# ADC_Driver.net
KiCad netlist of a schematic drawn in Altium Designer
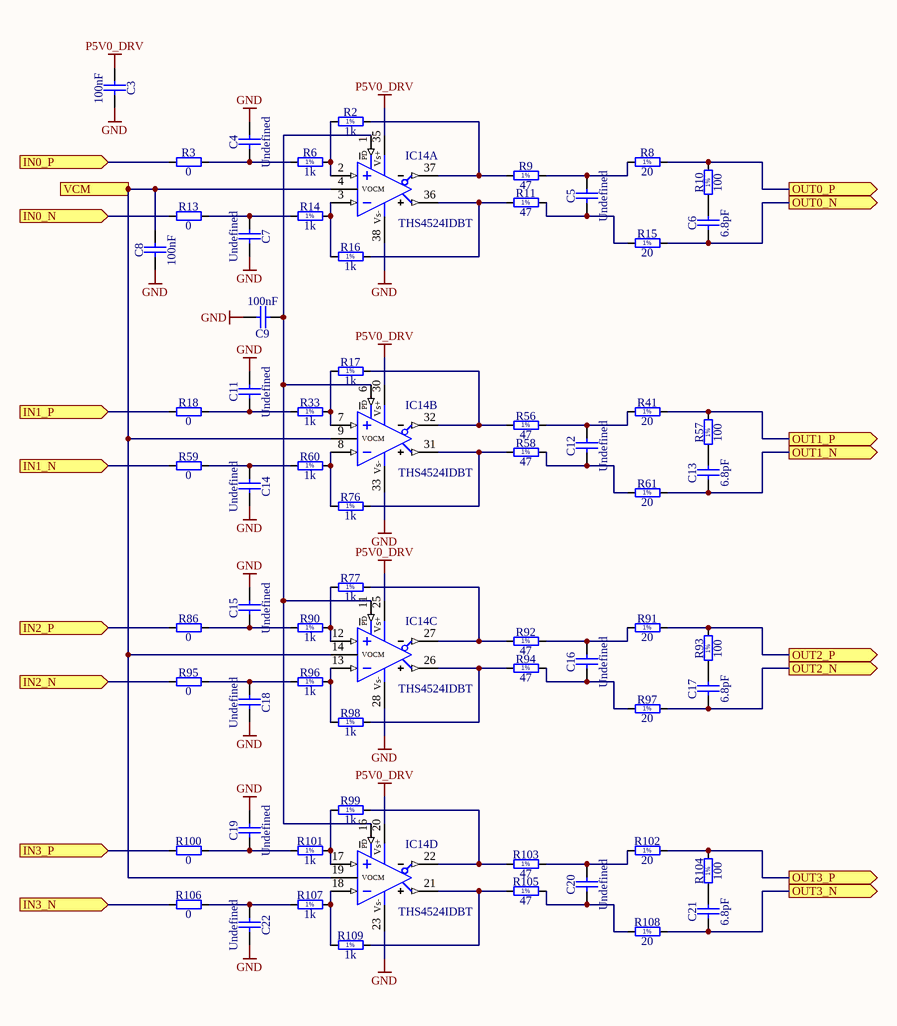
[diagram p0: ADC_Driver.SchDoc]

(export (version "E")
  (design (tool "Eeschema 10.0.6"))
  (components
    (comp (ref "C3")
      (value "100nF")
      (footprint "CAPC0603X33N")
      (description "Non-polarised capacitor")
      (fields
        (field (name "PART NUMBER") "CC0201_100NF_6.3V_10%_X5R")
        (field (name "VOLTAGE") "6.3V")
        (field (name "AUTHOR") "CERN DEM JLC")
      )
      (libsource (lib "Capacitors") (part "Capacitor - non polarized"))
    )
    (comp (ref "C4")
      (value "Undefined")
      (footprint "CAPC1005X55N")
      (description "Non-polarised capacitor")
      (fields (field (name "PART NUMBER") "CC0402_NO-VALUE") (field (name "AUTHOR") "CERN DEM JLC"))
      (libsource (lib "Capacitors") (part "Capacitor - non polarized"))
    )
    (comp (ref "C5")
      (value "Undefined")
      (footprint "CAPC1005X55N")
      (description "Non-polarised capacitor")
      (fields (field (name "PART NUMBER") "CC0402_NO-VALUE") (field (name "AUTHOR") "CERN DEM JLC"))
      (libsource (lib "Capacitors") (part "Capacitor - non polarized"))
    )
    (comp (ref "C6")
      (value "6.8pF")
      (footprint "CAPC1005X70N")
      (description "Non-polarised capacitor")
      (fields
        (field (name "PART NUMBER") "CC0402_6.8PF_50V_0.25PF_C0G_VISHAY_VJ_NON-MAGNETIC")
        (field (name "VOLTAGE") "50V")
        (field (name "AUTHOR") "CERN DEM MR")
      )
      (libsource (lib "Capacitors") (part "Capacitor - non polarized"))
    )
    (comp (ref "C7")
      (value "Undefined")
      (footprint "CAPC1005X55N")
      (description "Non-polarised capacitor")
      (fields (field (name "PART NUMBER") "CC0402_NO-VALUE") (field (name "AUTHOR") "CERN DEM JLC"))
      (libsource (lib "Capacitors") (part "Capacitor - non polarized"))
    )
    (comp (ref "C8")
      (value "100nF")
      (footprint "CAPC0603X33N")
      (description "Non-polarised capacitor")
      (fields
        (field (name "PART NUMBER") "CC0201_100NF_6.3V_10%_X5R")
        (field (name "VOLTAGE") "6.3V")
        (field (name "AUTHOR") "CERN DEM JLC")
      )
      (libsource (lib "Capacitors") (part "Capacitor - non polarized"))
    )
    (comp (ref "C9")
      (value "100nF")
      (footprint "CAPC0603X33N")
      (description "Non-polarised capacitor")
      (fields
        (field (name "PART NUMBER") "CC0201_100NF_6.3V_10%_X5R")
        (field (name "VOLTAGE") "6.3V")
        (field (name "AUTHOR") "CERN DEM JLC")
      )
      (libsource (lib "Capacitors") (part "Capacitor - non polarized"))
    )
    (comp (ref "C11")
      (value "Undefined")
      (footprint "CAPC1005X55N")
      (description "Non-polarised capacitor")
      (fields (field (name "PART NUMBER") "CC0402_NO-VALUE") (field (name "AUTHOR") "CERN DEM JLC"))
      (libsource (lib "Capacitors") (part "Capacitor - non polarized"))
    )
    (comp (ref "C12")
      (value "Undefined")
      (footprint "CAPC1005X55N")
      (description "Non-polarised capacitor")
      (fields (field (name "PART NUMBER") "CC0402_NO-VALUE") (field (name "AUTHOR") "CERN DEM JLC"))
      (libsource (lib "Capacitors") (part "Capacitor - non polarized"))
    )
    (comp (ref "C13")
      (value "6.8pF")
      (footprint "CAPC1005X70N")
      (description "Non-polarised capacitor")
      (fields
        (field (name "PART NUMBER") "CC0402_6.8PF_50V_0.25PF_C0G_VISHAY_VJ_NON-MAGNETIC")
        (field (name "VOLTAGE") "50V")
        (field (name "AUTHOR") "CERN DEM MR")
      )
      (libsource (lib "Capacitors") (part "Capacitor - non polarized"))
    )
    (comp (ref "C14")
      (value "Undefined")
      (footprint "CAPC1005X55N")
      (description "Non-polarised capacitor")
      (fields (field (name "PART NUMBER") "CC0402_NO-VALUE") (field (name "AUTHOR") "CERN DEM JLC"))
      (libsource (lib "Capacitors") (part "Capacitor - non polarized"))
    )
    (comp (ref "C15")
      (value "Undefined")
      (footprint "CAPC1005X55N")
      (description "Non-polarised capacitor")
      (fields (field (name "PART NUMBER") "CC0402_NO-VALUE") (field (name "AUTHOR") "CERN DEM JLC"))
      (libsource (lib "Capacitors") (part "Capacitor - non polarized"))
    )
    (comp (ref "C16")
      (value "Undefined")
      (footprint "CAPC1005X55N")
      (description "Non-polarised capacitor")
      (fields (field (name "PART NUMBER") "CC0402_NO-VALUE") (field (name "AUTHOR") "CERN DEM JLC"))
      (libsource (lib "Capacitors") (part "Capacitor - non polarized"))
    )
    (comp (ref "C17")
      (value "6.8pF")
      (footprint "CAPC1005X70N")
      (description "Non-polarised capacitor")
      (fields
        (field (name "PART NUMBER") "CC0402_6.8PF_50V_0.25PF_C0G_VISHAY_VJ_NON-MAGNETIC")
        (field (name "VOLTAGE") "50V")
        (field (name "AUTHOR") "CERN DEM MR")
      )
      (libsource (lib "Capacitors") (part "Capacitor - non polarized"))
    )
    (comp (ref "C18")
      (value "Undefined")
      (footprint "CAPC1005X55N")
      (description "Non-polarised capacitor")
      (fields (field (name "PART NUMBER") "CC0402_NO-VALUE") (field (name "AUTHOR") "CERN DEM JLC"))
      (libsource (lib "Capacitors") (part "Capacitor - non polarized"))
    )
    (comp (ref "C19")
      (value "Undefined")
      (footprint "CAPC1005X55N")
      (description "Non-polarised capacitor")
      (fields (field (name "PART NUMBER") "CC0402_NO-VALUE") (field (name "AUTHOR") "CERN DEM JLC"))
      (libsource (lib "Capacitors") (part "Capacitor - non polarized"))
    )
    (comp (ref "C20")
      (value "Undefined")
      (footprint "CAPC1005X55N")
      (description "Non-polarised capacitor")
      (fields (field (name "PART NUMBER") "CC0402_NO-VALUE") (field (name "AUTHOR") "CERN DEM JLC"))
      (libsource (lib "Capacitors") (part "Capacitor - non polarized"))
    )
    (comp (ref "C21")
      (value "6.8pF")
      (footprint "CAPC1005X70N")
      (description "Non-polarised capacitor")
      (fields
        (field (name "PART NUMBER") "CC0402_6.8PF_50V_0.25PF_C0G_VISHAY_VJ_NON-MAGNETIC")
        (field (name "VOLTAGE") "50V")
        (field (name "AUTHOR") "CERN DEM MR")
      )
      (libsource (lib "Capacitors") (part "Capacitor - non polarized"))
    )
    (comp (ref "C22")
      (value "Undefined")
      (footprint "CAPC1005X55N")
      (description "Non-polarised capacitor")
      (fields (field (name "PART NUMBER") "CC0402_NO-VALUE") (field (name "AUTHOR") "CERN DEM JLC"))
      (libsource (lib "Capacitors") (part "Capacitor - non polarized"))
    )
    (comp (ref "IC14")
      (value "THS4524IDBT")
      (footprint "SOP50P640X120-38N")
      (description "Very Low Power Quad Channel Rail-to-Rail Output Fully Differential Amplifier")
      (fields (field (name "MANUFACTURER") "TEXAS INSTRUMENTS") (field (name "AUTHOR") "CERN DEM JLC"))
      (libsource (lib "ICs And Semiconductors") (part "THS4524"))
    )
    (comp (ref "R2")
      (value "1k")
      (footprint "RESC1005X40N")
      (description "Resistor - 1%")
      (fields
        (field (name "PART NUMBER") "R0402_1K_1%_0.0625W_100PPM")
        (field (name "POWER") "0.0625W")
        (field (name "AUTHOR") "CERN DEM JLC")
      )
      (libsource (lib "Resistors") (part "Resistor - 1%"))
    )
    (comp (ref "R3")
      (value "0")
      (footprint "RESC1005X40N")
      (description "Resistor")
      (fields
        (field (name "PART NUMBER") "R0402_0R_JUMPER")
        (field (name "MANUFACTURER") "GENERIC")
        (field (name "AUTHOR") "CERN DEM JLC")
      )
      (libsource (lib "Resistors") (part "Resistor"))
    )
    (comp (ref "R6")
      (value "1k")
      (footprint "RESC1005X40N")
      (description "Resistor - 1%")
      (fields
        (field (name "PART NUMBER") "R0402_1K_1%_0.0625W_100PPM")
        (field (name "POWER") "0.0625W")
        (field (name "AUTHOR") "CERN DEM JLC")
      )
      (libsource (lib "Resistors") (part "Resistor - 1%"))
    )
    (comp (ref "R8")
      (value "20")
      (footprint "RESC1005X40N")
      (description "Resistor - 1%")
      (fields
        (field (name "PART NUMBER") "R0402_20R_1%_0.0625W_100PPM")
        (field (name "POWER") "0.0625W")
        (field (name "AUTHOR") "CERN DEM JLC")
      )
      (libsource (lib "Resistors") (part "Resistor - 1%"))
    )
    (comp (ref "R9")
      (value "47")
      (footprint "RESC1005X40N")
      (description "Resistor - 1%")
      (fields
        (field (name "PART NUMBER") "R0402_47R_1%_0.0625W_100PPM")
        (field (name "POWER") "0.0625W")
        (field (name "AUTHOR") "CERN DEM JLC")
      )
      (libsource (lib "Resistors") (part "Resistor - 1%"))
    )
    (comp (ref "R10")
      (value "100")
      (footprint "RESC0603X28N")
      (description "Resistor - 1%")
      (fields
        (field (name "PART NUMBER") "R0201_100R_1%_0.05W_200PPM")
        (field (name "POWER") "0.05W")
        (field (name "AUTHOR") "CERN DEM JLC")
      )
      (libsource (lib "Resistors") (part "Resistor - 1%"))
    )
    (comp (ref "R11")
      (value "47")
      (footprint "RESC1005X40N")
      (description "Resistor - 1%")
      (fields
        (field (name "PART NUMBER") "R0402_47R_1%_0.0625W_100PPM")
        (field (name "POWER") "0.0625W")
        (field (name "AUTHOR") "CERN DEM JLC")
      )
      (libsource (lib "Resistors") (part "Resistor - 1%"))
    )
    (comp (ref "R13")
      (value "0")
      (footprint "RESC1005X40N")
      (description "Resistor")
      (fields
        (field (name "PART NUMBER") "R0402_0R_JUMPER")
        (field (name "MANUFACTURER") "GENERIC")
        (field (name "AUTHOR") "CERN DEM JLC")
      )
      (libsource (lib "Resistors") (part "Resistor"))
    )
    (comp (ref "R14")
      (value "1k")
      (footprint "RESC1005X40N")
      (description "Resistor - 1%")
      (fields
        (field (name "PART NUMBER") "R0402_1K_1%_0.0625W_100PPM")
        (field (name "POWER") "0.0625W")
        (field (name "AUTHOR") "CERN DEM JLC")
      )
      (libsource (lib "Resistors") (part "Resistor - 1%"))
    )
    (comp (ref "R15")
      (value "20")
      (footprint "RESC1005X40N")
      (description "Resistor - 1%")
      (fields
        (field (name "PART NUMBER") "R0402_20R_1%_0.0625W_100PPM")
        (field (name "POWER") "0.0625W")
        (field (name "AUTHOR") "CERN DEM JLC")
      )
      (libsource (lib "Resistors") (part "Resistor - 1%"))
    )
    (comp (ref "R16")
      (value "1k")
      (footprint "RESC1005X40N")
      (description "Resistor - 1%")
      (fields
        (field (name "PART NUMBER") "R0402_1K_1%_0.0625W_100PPM")
        (field (name "POWER") "0.0625W")
        (field (name "AUTHOR") "CERN DEM JLC")
      )
      (libsource (lib "Resistors") (part "Resistor - 1%"))
    )
    (comp (ref "R17")
      (value "1k")
      (footprint "RESC1005X40N")
      (description "Resistor - 1%")
      (fields
        (field (name "PART NUMBER") "R0402_1K_1%_0.0625W_100PPM")
        (field (name "POWER") "0.0625W")
        (field (name "AUTHOR") "CERN DEM JLC")
      )
      (libsource (lib "Resistors") (part "Resistor - 1%"))
    )
    (comp (ref "R18")
      (value "0")
      (footprint "RESC1005X40N")
      (description "Resistor")
      (fields
        (field (name "PART NUMBER") "R0402_0R_JUMPER")
        (field (name "MANUFACTURER") "GENERIC")
        (field (name "AUTHOR") "CERN DEM JLC")
      )
      (libsource (lib "Resistors") (part "Resistor"))
    )
    (comp (ref "R33")
      (value "1k")
      (footprint "RESC1005X40N")
      (description "Resistor - 1%")
      (fields
        (field (name "PART NUMBER") "R0402_1K_1%_0.0625W_100PPM")
        (field (name "POWER") "0.0625W")
        (field (name "AUTHOR") "CERN DEM JLC")
      )
      (libsource (lib "Resistors") (part "Resistor - 1%"))
    )
    (comp (ref "R41")
      (value "20")
      (footprint "RESC1005X40N")
      (description "Resistor - 1%")
      (fields
        (field (name "PART NUMBER") "R0402_20R_1%_0.0625W_100PPM")
        (field (name "POWER") "0.0625W")
        (field (name "AUTHOR") "CERN DEM JLC")
      )
      (libsource (lib "Resistors") (part "Resistor - 1%"))
    )
    (comp (ref "R56")
      (value "47")
      (footprint "RESC1005X40N")
      (description "Resistor - 1%")
      (fields
        (field (name "PART NUMBER") "R0402_47R_1%_0.0625W_100PPM")
        (field (name "POWER") "0.0625W")
        (field (name "AUTHOR") "CERN DEM JLC")
      )
      (libsource (lib "Resistors") (part "Resistor - 1%"))
    )
    (comp (ref "R57")
      (value "100")
      (footprint "RESC0603X28N")
      (description "Resistor - 1%")
      (fields
        (field (name "PART NUMBER") "R0201_100R_1%_0.05W_200PPM")
        (field (name "POWER") "0.05W")
        (field (name "AUTHOR") "CERN DEM JLC")
      )
      (libsource (lib "Resistors") (part "Resistor - 1%"))
    )
    (comp (ref "R58")
      (value "47")
      (footprint "RESC1005X40N")
      (description "Resistor - 1%")
      (fields
        (field (name "PART NUMBER") "R0402_47R_1%_0.0625W_100PPM")
        (field (name "POWER") "0.0625W")
        (field (name "AUTHOR") "CERN DEM JLC")
      )
      (libsource (lib "Resistors") (part "Resistor - 1%"))
    )
    (comp (ref "R59")
      (value "0")
      (footprint "RESC1005X40N")
      (description "Resistor")
      (fields
        (field (name "PART NUMBER") "R0402_0R_JUMPER")
        (field (name "MANUFACTURER") "GENERIC")
        (field (name "AUTHOR") "CERN DEM JLC")
      )
      (libsource (lib "Resistors") (part "Resistor"))
    )
    (comp (ref "R60")
      (value "1k")
      (footprint "RESC1005X40N")
      (description "Resistor - 1%")
      (fields
        (field (name "PART NUMBER") "R0402_1K_1%_0.0625W_100PPM")
        (field (name "POWER") "0.0625W")
        (field (name "AUTHOR") "CERN DEM JLC")
      )
      (libsource (lib "Resistors") (part "Resistor - 1%"))
    )
    (comp (ref "R61")
      (value "20")
      (footprint "RESC1005X40N")
      (description "Resistor - 1%")
      (fields
        (field (name "PART NUMBER") "R0402_20R_1%_0.0625W_100PPM")
        (field (name "POWER") "0.0625W")
        (field (name "AUTHOR") "CERN DEM JLC")
      )
      (libsource (lib "Resistors") (part "Resistor - 1%"))
    )
    (comp (ref "R76")
      (value "1k")
      (footprint "RESC1005X40N")
      (description "Resistor - 1%")
      (fields
        (field (name "PART NUMBER") "R0402_1K_1%_0.0625W_100PPM")
        (field (name "POWER") "0.0625W")
        (field (name "AUTHOR") "CERN DEM JLC")
      )
      (libsource (lib "Resistors") (part "Resistor - 1%"))
    )
    (comp (ref "R77")
      (value "1k")
      (footprint "RESC1005X40N")
      (description "Resistor - 1%")
      (fields
        (field (name "PART NUMBER") "R0402_1K_1%_0.0625W_100PPM")
        (field (name "POWER") "0.0625W")
        (field (name "AUTHOR") "CERN DEM JLC")
      )
      (libsource (lib "Resistors") (part "Resistor - 1%"))
    )
    (comp (ref "R86")
      (value "0")
      (footprint "RESC1005X40N")
      (description "Resistor")
      (fields
        (field (name "PART NUMBER") "R0402_0R_JUMPER")
        (field (name "MANUFACTURER") "GENERIC")
        (field (name "AUTHOR") "CERN DEM JLC")
      )
      (libsource (lib "Resistors") (part "Resistor"))
    )
    (comp (ref "R90")
      (value "1k")
      (footprint "RESC1005X40N")
      (description "Resistor - 1%")
      (fields
        (field (name "PART NUMBER") "R0402_1K_1%_0.0625W_100PPM")
        (field (name "POWER") "0.0625W")
        (field (name "AUTHOR") "CERN DEM JLC")
      )
      (libsource (lib "Resistors") (part "Resistor - 1%"))
    )
    (comp (ref "R91")
      (value "20")
      (footprint "RESC1005X40N")
      (description "Resistor - 1%")
      (fields
        (field (name "PART NUMBER") "R0402_20R_1%_0.0625W_100PPM")
        (field (name "POWER") "0.0625W")
        (field (name "AUTHOR") "CERN DEM JLC")
      )
      (libsource (lib "Resistors") (part "Resistor - 1%"))
    )
    (comp (ref "R92")
      (value "47")
      (footprint "RESC1005X40N")
      (description "Resistor - 1%")
      (fields
        (field (name "PART NUMBER") "R0402_47R_1%_0.0625W_100PPM")
        (field (name "POWER") "0.0625W")
        (field (name "AUTHOR") "CERN DEM JLC")
      )
      (libsource (lib "Resistors") (part "Resistor - 1%"))
    )
    (comp (ref "R93")
      (value "100")
      (footprint "RESC0603X28N")
      (description "Resistor - 1%")
      (fields
        (field (name "PART NUMBER") "R0201_100R_1%_0.05W_200PPM")
        (field (name "POWER") "0.05W")
        (field (name "AUTHOR") "CERN DEM JLC")
      )
      (libsource (lib "Resistors") (part "Resistor - 1%"))
    )
    (comp (ref "R94")
      (value "47")
      (footprint "RESC1005X40N")
      (description "Resistor - 1%")
      (fields
        (field (name "PART NUMBER") "R0402_47R_1%_0.0625W_100PPM")
        (field (name "POWER") "0.0625W")
        (field (name "AUTHOR") "CERN DEM JLC")
      )
      (libsource (lib "Resistors") (part "Resistor - 1%"))
    )
    (comp (ref "R95")
      (value "0")
      (footprint "RESC1005X40N")
      (description "Resistor")
      (fields
        (field (name "PART NUMBER") "R0402_0R_JUMPER")
        (field (name "MANUFACTURER") "GENERIC")
        (field (name "AUTHOR") "CERN DEM JLC")
      )
      (libsource (lib "Resistors") (part "Resistor"))
    )
    (comp (ref "R96")
      (value "1k")
      (footprint "RESC1005X40N")
      (description "Resistor - 1%")
      (fields
        (field (name "PART NUMBER") "R0402_1K_1%_0.0625W_100PPM")
        (field (name "POWER") "0.0625W")
        (field (name "AUTHOR") "CERN DEM JLC")
      )
      (libsource (lib "Resistors") (part "Resistor - 1%"))
    )
    (comp (ref "R97")
      (value "20")
      (footprint "RESC1005X40N")
      (description "Resistor - 1%")
      (fields
        (field (name "PART NUMBER") "R0402_20R_1%_0.0625W_100PPM")
        (field (name "POWER") "0.0625W")
        (field (name "AUTHOR") "CERN DEM JLC")
      )
      (libsource (lib "Resistors") (part "Resistor - 1%"))
    )
    (comp (ref "R98")
      (value "1k")
      (footprint "RESC1005X40N")
      (description "Resistor - 1%")
      (fields
        (field (name "PART NUMBER") "R0402_1K_1%_0.0625W_100PPM")
        (field (name "POWER") "0.0625W")
        (field (name "AUTHOR") "CERN DEM JLC")
      )
      (libsource (lib "Resistors") (part "Resistor - 1%"))
    )
    (comp (ref "R99")
      (value "1k")
      (footprint "RESC1005X40N")
      (description "Resistor - 1%")
      (fields
        (field (name "PART NUMBER") "R0402_1K_1%_0.0625W_100PPM")
        (field (name "POWER") "0.0625W")
        (field (name "AUTHOR") "CERN DEM JLC")
      )
      (libsource (lib "Resistors") (part "Resistor - 1%"))
    )
    (comp (ref "R100")
      (value "0")
      (footprint "RESC1005X40N")
      (description "Resistor")
      (fields
        (field (name "PART NUMBER") "R0402_0R_JUMPER")
        (field (name "MANUFACTURER") "GENERIC")
        (field (name "AUTHOR") "CERN DEM JLC")
      )
      (libsource (lib "Resistors") (part "Resistor"))
    )
    (comp (ref "R101")
      (value "1k")
      (footprint "RESC1005X40N")
      (description "Resistor - 1%")
      (fields
        (field (name "PART NUMBER") "R0402_1K_1%_0.0625W_100PPM")
        (field (name "POWER") "0.0625W")
        (field (name "AUTHOR") "CERN DEM JLC")
      )
      (libsource (lib "Resistors") (part "Resistor - 1%"))
    )
    (comp (ref "R102")
      (value "20")
      (footprint "RESC1005X40N")
      (description "Resistor - 1%")
      (fields
        (field (name "PART NUMBER") "R0402_20R_1%_0.0625W_100PPM")
        (field (name "POWER") "0.0625W")
        (field (name "AUTHOR") "CERN DEM JLC")
      )
      (libsource (lib "Resistors") (part "Resistor - 1%"))
    )
    (comp (ref "R103")
      (value "47")
      (footprint "RESC1005X40N")
      (description "Resistor - 1%")
      (fields
        (field (name "PART NUMBER") "R0402_47R_1%_0.0625W_100PPM")
        (field (name "POWER") "0.0625W")
        (field (name "AUTHOR") "CERN DEM JLC")
      )
      (libsource (lib "Resistors") (part "Resistor - 1%"))
    )
    (comp (ref "R104")
      (value "100")
      (footprint "RESC0603X28N")
      (description "Resistor - 1%")
      (fields
        (field (name "PART NUMBER") "R0201_100R_1%_0.05W_200PPM")
        (field (name "POWER") "0.05W")
        (field (name "AUTHOR") "CERN DEM JLC")
      )
      (libsource (lib "Resistors") (part "Resistor - 1%"))
    )
    (comp (ref "R105")
      (value "47")
      (footprint "RESC1005X40N")
      (description "Resistor - 1%")
      (fields
        (field (name "PART NUMBER") "R0402_47R_1%_0.0625W_100PPM")
        (field (name "POWER") "0.0625W")
        (field (name "AUTHOR") "CERN DEM JLC")
      )
      (libsource (lib "Resistors") (part "Resistor - 1%"))
    )
    (comp (ref "R106")
      (value "0")
      (footprint "RESC1005X40N")
      (description "Resistor")
      (fields
        (field (name "PART NUMBER") "R0402_0R_JUMPER")
        (field (name "MANUFACTURER") "GENERIC")
        (field (name "AUTHOR") "CERN DEM JLC")
      )
      (libsource (lib "Resistors") (part "Resistor"))
    )
    (comp (ref "R107")
      (value "1k")
      (footprint "RESC1005X40N")
      (description "Resistor - 1%")
      (fields
        (field (name "PART NUMBER") "R0402_1K_1%_0.0625W_100PPM")
        (field (name "POWER") "0.0625W")
        (field (name "AUTHOR") "CERN DEM JLC")
      )
      (libsource (lib "Resistors") (part "Resistor - 1%"))
    )
    (comp (ref "R108")
      (value "20")
      (footprint "RESC1005X40N")
      (description "Resistor - 1%")
      (fields
        (field (name "PART NUMBER") "R0402_20R_1%_0.0625W_100PPM")
        (field (name "POWER") "0.0625W")
        (field (name "AUTHOR") "CERN DEM JLC")
      )
      (libsource (lib "Resistors") (part "Resistor - 1%"))
    )
    (comp (ref "R109")
      (value "1k")
      (footprint "RESC1005X40N")
      (description "Resistor - 1%")
      (fields
        (field (name "PART NUMBER") "R0402_1K_1%_0.0625W_100PPM")
        (field (name "POWER") "0.0625W")
        (field (name "AUTHOR") "CERN DEM JLC")
      )
      (libsource (lib "Resistors") (part "Resistor - 1%"))
    )
  )
  (nets
    (net (code "1") (name "/IN0_N") (class "Default")
      (node (ref "R13") (pin "1") (pinfunction "1_1") (pintype "passive"))
    )
    (net (code "2") (name "/IN0_P") (class "Default")
      (node (ref "R3") (pin "1") (pinfunction "1_1") (pintype "passive"))
    )
    (net (code "3") (name "/IN1_N") (class "Default")
      (node (ref "R59") (pin "1") (pinfunction "1_1") (pintype "passive"))
    )
    (net (code "4") (name "/IN1_P") (class "Default")
      (node (ref "R18") (pin "1") (pinfunction "1_1") (pintype "passive"))
    )
    (net (code "5") (name "/IN2_N") (class "Default")
      (node (ref "R95") (pin "1") (pinfunction "1_1") (pintype "passive"))
    )
    (net (code "6") (name "/IN2_P") (class "Default")
      (node (ref "R86") (pin "1") (pinfunction "1_1") (pintype "passive"))
    )
    (net (code "7") (name "/IN3_N") (class "Default")
      (node (ref "R106") (pin "1") (pinfunction "1_1") (pintype "passive"))
    )
    (net (code "8") (name "/IN3_P") (class "Default")
      (node (ref "R100") (pin "1") (pinfunction "1_1") (pintype "passive"))
    )
    (net (code "9") (name "/OUT0_N") (class "Default")
      (node (ref "C6") (pin "1") (pinfunction "1_1") (pintype "passive"))
      (node (ref "R15") (pin "2") (pinfunction "2_2") (pintype "passive"))
    )
    (net (code "10") (name "/OUT0_P") (class "Default")
      (node (ref "R10") (pin "2") (pinfunction "2_2") (pintype "passive"))
      (node (ref "R8") (pin "2") (pinfunction "2_2") (pintype "passive"))
    )
    (net (code "11") (name "/OUT1_N") (class "Default")
      (node (ref "C13") (pin "1") (pinfunction "1_1") (pintype "passive"))
      (node (ref "R61") (pin "2") (pinfunction "2_2") (pintype "passive"))
    )
    (net (code "12") (name "/OUT1_P") (class "Default")
      (node (ref "R41") (pin "2") (pinfunction "2_2") (pintype "passive"))
      (node (ref "R57") (pin "2") (pinfunction "2_2") (pintype "passive"))
    )
    (net (code "13") (name "/OUT2_N") (class "Default")
      (node (ref "C17") (pin "1") (pinfunction "1_1") (pintype "passive"))
      (node (ref "R97") (pin "2") (pinfunction "2_2") (pintype "passive"))
    )
    (net (code "14") (name "/OUT2_P") (class "Default")
      (node (ref "R91") (pin "2") (pinfunction "2_2") (pintype "passive"))
      (node (ref "R93") (pin "2") (pinfunction "2_2") (pintype "passive"))
    )
    (net (code "15") (name "/OUT3_N") (class "Default")
      (node (ref "C21") (pin "1") (pinfunction "1_1") (pintype "passive"))
      (node (ref "R108") (pin "2") (pinfunction "2_2") (pintype "passive"))
    )
    (net (code "16") (name "/OUT3_P") (class "Default")
      (node (ref "R102") (pin "2") (pinfunction "2_2") (pintype "passive"))
      (node (ref "R104") (pin "2") (pinfunction "2_2") (pintype "passive"))
    )
    (net (code "17") (name "/VCM") (class "Default")
      (node (ref "C8") (pin "2") (pinfunction "2_2") (pintype "passive"))
      (node (ref "IC14") (pin "14") (pinfunction "VOCM_14") (pintype "passive"))
      (node (ref "IC14") (pin "19") (pinfunction "VOCM_19") (pintype "passive"))
      (node (ref "IC14") (pin "4") (pinfunction "VOCM_4") (pintype "passive"))
      (node (ref "IC14") (pin "9") (pinfunction "VOCM_9") (pintype "passive"))
    )
    (net (code "18") (name "GND") (class "Default")
      (node (ref "C11") (pin "2") (pinfunction "2_2") (pintype "passive"))
      (node (ref "C14") (pin "2") (pinfunction "2_2") (pintype "passive"))
      (node (ref "C15") (pin "2") (pinfunction "2_2") (pintype "passive"))
      (node (ref "C18") (pin "2") (pinfunction "2_2") (pintype "passive"))
      (node (ref "C19") (pin "2") (pinfunction "2_2") (pintype "passive"))
      (node (ref "C22") (pin "2") (pinfunction "2_2") (pintype "passive"))
      (node (ref "C3") (pin "2") (pinfunction "2_2") (pintype "passive"))
      (node (ref "C4") (pin "2") (pinfunction "2_2") (pintype "passive"))
      (node (ref "C7") (pin "2") (pinfunction "2_2") (pintype "passive"))
      (node (ref "C8") (pin "1") (pinfunction "1_1") (pintype "passive"))
      (node (ref "C9") (pin "2") (pinfunction "2_2") (pintype "passive"))
      (node (ref "IC14") (pin "23") (pinfunction "Vs-_23") (pintype "power_in"))
      (node (ref "IC14") (pin "28") (pinfunction "Vs-_28") (pintype "power_in"))
      (node (ref "IC14") (pin "33") (pinfunction "Vs-_33") (pintype "power_in"))
      (node (ref "IC14") (pin "38") (pinfunction "Vs-_38") (pintype "power_in"))
    )
    (net (code "19") (name "Net-(C4-Pad1)") (class "Default")
      (node (ref "C4") (pin "1") (pinfunction "1_1") (pintype "passive"))
      (node (ref "R3") (pin "2") (pinfunction "2_2") (pintype "passive"))
      (node (ref "R6") (pin "1") (pinfunction "1_1") (pintype "passive"))
    )
    (net (code "20") (name "Net-(C5-Pad1)") (class "Default")
      (node (ref "C5") (pin "1") (pinfunction "1_1") (pintype "passive"))
      (node (ref "R11") (pin "2") (pinfunction "2_2") (pintype "passive"))
      (node (ref "R15") (pin "1") (pinfunction "1_1") (pintype "passive"))
    )
    (net (code "21") (name "Net-(C5-Pad2)") (class "Default")
      (node (ref "C5") (pin "2") (pinfunction "2_2") (pintype "passive"))
      (node (ref "R8") (pin "1") (pinfunction "1_1") (pintype "passive"))
      (node (ref "R9") (pin "2") (pinfunction "2_2") (pintype "passive"))
    )
    (net (code "22") (name "Net-(C6-Pad2)") (class "Default")
      (node (ref "C6") (pin "2") (pinfunction "2_2") (pintype "passive"))
      (node (ref "R10") (pin "1") (pinfunction "1_1") (pintype "passive"))
    )
    (net (code "23") (name "Net-(C7-Pad1)") (class "Default")
      (node (ref "C7") (pin "1") (pinfunction "1_1") (pintype "passive"))
      (node (ref "R13") (pin "2") (pinfunction "2_2") (pintype "passive"))
      (node (ref "R14") (pin "1") (pinfunction "1_1") (pintype "passive"))
    )
    (net (code "24") (name "Net-(C11-Pad1)") (class "Default")
      (node (ref "C11") (pin "1") (pinfunction "1_1") (pintype "passive"))
      (node (ref "R18") (pin "2") (pinfunction "2_2") (pintype "passive"))
      (node (ref "R33") (pin "1") (pinfunction "1_1") (pintype "passive"))
    )
    (net (code "25") (name "Net-(C12-Pad1)") (class "Default")
      (node (ref "C12") (pin "1") (pinfunction "1_1") (pintype "passive"))
      (node (ref "R58") (pin "2") (pinfunction "2_2") (pintype "passive"))
      (node (ref "R61") (pin "1") (pinfunction "1_1") (pintype "passive"))
    )
    (net (code "26") (name "Net-(C12-Pad2)") (class "Default")
      (node (ref "C12") (pin "2") (pinfunction "2_2") (pintype "passive"))
      (node (ref "R41") (pin "1") (pinfunction "1_1") (pintype "passive"))
      (node (ref "R56") (pin "2") (pinfunction "2_2") (pintype "passive"))
    )
    (net (code "27") (name "Net-(C13-Pad2)") (class "Default")
      (node (ref "C13") (pin "2") (pinfunction "2_2") (pintype "passive"))
      (node (ref "R57") (pin "1") (pinfunction "1_1") (pintype "passive"))
    )
    (net (code "28") (name "Net-(C14-Pad1)") (class "Default")
      (node (ref "C14") (pin "1") (pinfunction "1_1") (pintype "passive"))
      (node (ref "R59") (pin "2") (pinfunction "2_2") (pintype "passive"))
      (node (ref "R60") (pin "1") (pinfunction "1_1") (pintype "passive"))
    )
    (net (code "29") (name "Net-(C15-Pad1)") (class "Default")
      (node (ref "C15") (pin "1") (pinfunction "1_1") (pintype "passive"))
      (node (ref "R86") (pin "2") (pinfunction "2_2") (pintype "passive"))
      (node (ref "R90") (pin "1") (pinfunction "1_1") (pintype "passive"))
    )
    (net (code "30") (name "Net-(C16-Pad1)") (class "Default")
      (node (ref "C16") (pin "1") (pinfunction "1_1") (pintype "passive"))
      (node (ref "R94") (pin "2") (pinfunction "2_2") (pintype "passive"))
      (node (ref "R97") (pin "1") (pinfunction "1_1") (pintype "passive"))
    )
    (net (code "31") (name "Net-(C16-Pad2)") (class "Default")
      (node (ref "C16") (pin "2") (pinfunction "2_2") (pintype "passive"))
      (node (ref "R91") (pin "1") (pinfunction "1_1") (pintype "passive"))
      (node (ref "R92") (pin "2") (pinfunction "2_2") (pintype "passive"))
    )
    (net (code "32") (name "Net-(C17-Pad2)") (class "Default")
      (node (ref "C17") (pin "2") (pinfunction "2_2") (pintype "passive"))
      (node (ref "R93") (pin "1") (pinfunction "1_1") (pintype "passive"))
    )
    (net (code "33") (name "Net-(C18-Pad1)") (class "Default")
      (node (ref "C18") (pin "1") (pinfunction "1_1") (pintype "passive"))
      (node (ref "R95") (pin "2") (pinfunction "2_2") (pintype "passive"))
      (node (ref "R96") (pin "1") (pinfunction "1_1") (pintype "passive"))
    )
    (net (code "34") (name "Net-(C19-Pad1)") (class "Default")
      (node (ref "C19") (pin "1") (pinfunction "1_1") (pintype "passive"))
      (node (ref "R100") (pin "2") (pinfunction "2_2") (pintype "passive"))
      (node (ref "R101") (pin "1") (pinfunction "1_1") (pintype "passive"))
    )
    (net (code "35") (name "Net-(C20-Pad1)") (class "Default")
      (node (ref "C20") (pin "1") (pinfunction "1_1") (pintype "passive"))
      (node (ref "R105") (pin "2") (pinfunction "2_2") (pintype "passive"))
      (node (ref "R108") (pin "1") (pinfunction "1_1") (pintype "passive"))
    )
    (net (code "36") (name "Net-(C20-Pad2)") (class "Default")
      (node (ref "C20") (pin "2") (pinfunction "2_2") (pintype "passive"))
      (node (ref "R102") (pin "1") (pinfunction "1_1") (pintype "passive"))
      (node (ref "R103") (pin "2") (pinfunction "2_2") (pintype "passive"))
    )
    (net (code "37") (name "Net-(C21-Pad2)") (class "Default")
      (node (ref "C21") (pin "2") (pinfunction "2_2") (pintype "passive"))
      (node (ref "R104") (pin "1") (pinfunction "1_1") (pintype "passive"))
    )
    (net (code "38") (name "Net-(C22-Pad1)") (class "Default")
      (node (ref "C22") (pin "1") (pinfunction "1_1") (pintype "passive"))
      (node (ref "R106") (pin "2") (pinfunction "2_2") (pintype "passive"))
      (node (ref "R107") (pin "1") (pinfunction "1_1") (pintype "passive"))
    )
    (net (code "39") (name "Net-(IC14A-IN+)") (class "Default")
      (node (ref "IC14") (pin "2") (pinfunction "IN+_2") (pintype "input"))
      (node (ref "R2") (pin "1") (pinfunction "1_1") (pintype "passive"))
      (node (ref "R6") (pin "2") (pinfunction "2_2") (pintype "passive"))
    )
    (net (code "40") (name "Net-(IC14A-IN-)") (class "Default")
      (node (ref "IC14") (pin "3") (pinfunction "IN-_3") (pintype "input"))
      (node (ref "R14") (pin "2") (pinfunction "2_2") (pintype "passive"))
      (node (ref "R16") (pin "1") (pinfunction "1_1") (pintype "passive"))
    )
    (net (code "41") (name "Net-(IC14A-PD)") (class "Default")
      (node (ref "C9") (pin "1") (pinfunction "1_1") (pintype "passive"))
      (node (ref "IC14") (pin "1") (pinfunction "PD_1") (pintype "input"))
      (node (ref "IC14") (pin "11") (pinfunction "PD_11") (pintype "input"))
      (node (ref "IC14") (pin "16") (pinfunction "PD_16") (pintype "input"))
      (node (ref "IC14") (pin "6") (pinfunction "PD_6") (pintype "input"))
    )
    (net (code "42") (name "Net-(IC14A-VOUT+)") (class "Default")
      (node (ref "IC14") (pin "36") (pinfunction "VOUT+_36") (pintype "output"))
      (node (ref "R11") (pin "1") (pinfunction "1_1") (pintype "passive"))
      (node (ref "R16") (pin "2") (pinfunction "2_2") (pintype "passive"))
    )
    (net (code "43") (name "Net-(IC14A-VOUT-)") (class "Default")
      (node (ref "IC14") (pin "37") (pinfunction "VOUT-_37") (pintype "output"))
      (node (ref "R2") (pin "2") (pinfunction "2_2") (pintype "passive"))
      (node (ref "R9") (pin "1") (pinfunction "1_1") (pintype "passive"))
    )
    (net (code "44") (name "Net-(IC14B-IN+)") (class "Default")
      (node (ref "IC14") (pin "7") (pinfunction "IN+_7") (pintype "input"))
      (node (ref "R17") (pin "1") (pinfunction "1_1") (pintype "passive"))
      (node (ref "R33") (pin "2") (pinfunction "2_2") (pintype "passive"))
    )
    (net (code "45") (name "Net-(IC14B-IN-)") (class "Default")
      (node (ref "IC14") (pin "8") (pinfunction "IN-_8") (pintype "input"))
      (node (ref "R60") (pin "2") (pinfunction "2_2") (pintype "passive"))
      (node (ref "R76") (pin "1") (pinfunction "1_1") (pintype "passive"))
    )
    (net (code "46") (name "Net-(IC14B-VOUT+)") (class "Default")
      (node (ref "IC14") (pin "31") (pinfunction "VOUT+_31") (pintype "output"))
      (node (ref "R58") (pin "1") (pinfunction "1_1") (pintype "passive"))
      (node (ref "R76") (pin "2") (pinfunction "2_2") (pintype "passive"))
    )
    (net (code "47") (name "Net-(IC14B-VOUT-)") (class "Default")
      (node (ref "IC14") (pin "32") (pinfunction "VOUT-_32") (pintype "output"))
      (node (ref "R17") (pin "2") (pinfunction "2_2") (pintype "passive"))
      (node (ref "R56") (pin "1") (pinfunction "1_1") (pintype "passive"))
    )
    (net (code "48") (name "Net-(IC14C-IN+)") (class "Default")
      (node (ref "IC14") (pin "12") (pinfunction "IN+_12") (pintype "input"))
      (node (ref "R77") (pin "1") (pinfunction "1_1") (pintype "passive"))
      (node (ref "R90") (pin "2") (pinfunction "2_2") (pintype "passive"))
    )
    (net (code "49") (name "Net-(IC14C-IN-)") (class "Default")
      (node (ref "IC14") (pin "13") (pinfunction "IN-_13") (pintype "input"))
      (node (ref "R96") (pin "2") (pinfunction "2_2") (pintype "passive"))
      (node (ref "R98") (pin "1") (pinfunction "1_1") (pintype "passive"))
    )
    (net (code "50") (name "Net-(IC14C-VOUT+)") (class "Default")
      (node (ref "IC14") (pin "26") (pinfunction "VOUT+_26") (pintype "output"))
      (node (ref "R94") (pin "1") (pinfunction "1_1") (pintype "passive"))
      (node (ref "R98") (pin "2") (pinfunction "2_2") (pintype "passive"))
    )
    (net (code "51") (name "Net-(IC14C-VOUT-)") (class "Default")
      (node (ref "IC14") (pin "27") (pinfunction "VOUT-_27") (pintype "output"))
      (node (ref "R77") (pin "2") (pinfunction "2_2") (pintype "passive"))
      (node (ref "R92") (pin "1") (pinfunction "1_1") (pintype "passive"))
    )
    (net (code "52") (name "Net-(IC14D-IN+)") (class "Default")
      (node (ref "IC14") (pin "17") (pinfunction "IN+_17") (pintype "input"))
      (node (ref "R101") (pin "2") (pinfunction "2_2") (pintype "passive"))
      (node (ref "R99") (pin "1") (pinfunction "1_1") (pintype "passive"))
    )
    (net (code "53") (name "Net-(IC14D-IN-)") (class "Default")
      (node (ref "IC14") (pin "18") (pinfunction "IN-_18") (pintype "input"))
      (node (ref "R107") (pin "2") (pinfunction "2_2") (pintype "passive"))
      (node (ref "R109") (pin "1") (pinfunction "1_1") (pintype "passive"))
    )
    (net (code "54") (name "Net-(IC14D-VOUT+)") (class "Default")
      (node (ref "IC14") (pin "21") (pinfunction "VOUT+_21") (pintype "output"))
      (node (ref "R105") (pin "1") (pinfunction "1_1") (pintype "passive"))
      (node (ref "R109") (pin "2") (pinfunction "2_2") (pintype "passive"))
    )
    (net (code "55") (name "Net-(IC14D-VOUT-)") (class "Default")
      (node (ref "IC14") (pin "22") (pinfunction "VOUT-_22") (pintype "output"))
      (node (ref "R103") (pin "1") (pinfunction "1_1") (pintype "passive"))
      (node (ref "R99") (pin "2") (pinfunction "2_2") (pintype "passive"))
    )
    (net (code "56") (name "P5V0_DRV") (class "Default")
      (node (ref "C3") (pin "1") (pinfunction "1_1") (pintype "passive"))
      (node (ref "IC14") (pin "20") (pinfunction "Vs+_20") (pintype "power_in"))
      (node (ref "IC14") (pin "25") (pinfunction "Vs+_25") (pintype "power_in"))
      (node (ref "IC14") (pin "30") (pinfunction "Vs+_30") (pintype "power_in"))
      (node (ref "IC14") (pin "35") (pinfunction "Vs+_35") (pintype "power_in"))
    )
  )
)
